# Sintetizador_BA_Analog.net
KiCad netlist of a schematic drawn in Altium Designer
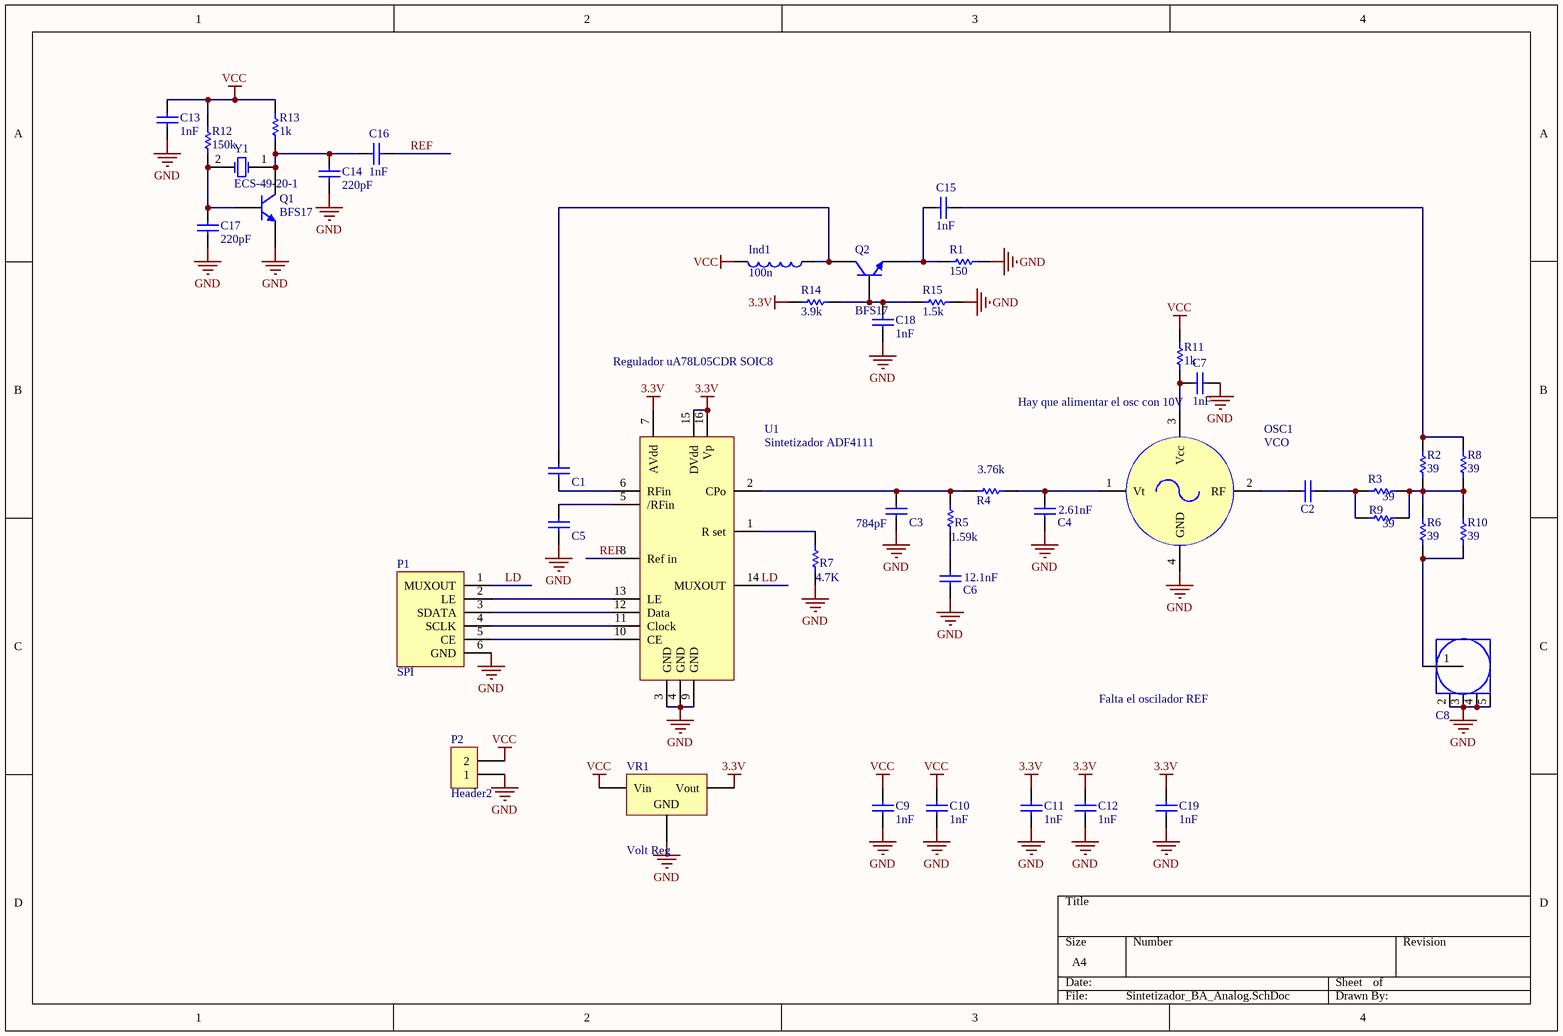
[diagram p0: Sintetizador_BA_Analog.SchDoc]

(export (version "E")
  (design (tool "Eeschema 10.0.6"))
  (components
    (comp (ref "C1") (value "Capacitor") (footprint "0805_CAP") (libsource (lib "epf") (part "Cap")))
    (comp (ref "C2") (value "Capacitor") (footprint "0805_CAP") (libsource (lib "epf") (part "Cap")))
    (comp (ref "C3")
      (value "784pF")
      (footprint "0805_CAP")
      (fields (field (name "Comment") "Capacitor"))
      (libsource (lib "epf") (part "Cap"))
    )
    (comp (ref "C4")
      (value "2.61nF")
      (footprint "0805_CAP")
      (fields (field (name "Comment") "Capacitor"))
      (libsource (lib "epf") (part "Cap"))
    )
    (comp (ref "C5") (value "Capacitor") (footprint "0805_CAP") (libsource (lib "epf") (part "Cap")))
    (comp (ref "C6")
      (value "12.1nF")
      (footprint "0805_CAP")
      (fields (field (name "Comment") "Capacitor"))
      (libsource (lib "epf") (part "Cap"))
    )
    (comp (ref "C7")
      (value "1nF")
      (footprint "0805_CAP")
      (fields (field (name "Comment") "Capacitor"))
      (libsource (lib "epf") (part "Cap"))
    )
    (comp (ref "C8") (value "SMA") (footprint "SMAL2") (libsource (lib "epf") (part "SMA")))
    (comp (ref "C9")
      (value "1nF")
      (footprint "0805_CAP")
      (fields (field (name "Comment") "Capacitor"))
      (libsource (lib "epf") (part "Cap"))
    )
    (comp (ref "C10")
      (value "1nF")
      (footprint "0805_CAP")
      (fields (field (name "Comment") "Capacitor"))
      (libsource (lib "epf") (part "Cap"))
    )
    (comp (ref "C11")
      (value "1nF")
      (footprint "0805_CAP")
      (fields (field (name "Comment") "Capacitor"))
      (libsource (lib "epf") (part "Cap"))
    )
    (comp (ref "C12")
      (value "1nF")
      (footprint "0805_CAP")
      (fields (field (name "Comment") "Capacitor"))
      (libsource (lib "epf") (part "Cap"))
    )
    (comp (ref "C13")
      (value "1nF")
      (footprint "0805_CAP")
      (fields (field (name "Comment") "Capacitor"))
      (libsource (lib "epf") (part "Cap"))
    )
    (comp (ref "C14")
      (value "220pF")
      (footprint "0805_CAP")
      (fields (field (name "Comment") "Capacitor"))
      (libsource (lib "epf") (part "Cap"))
    )
    (comp (ref "C15")
      (value "1nF")
      (footprint "0805_CAP")
      (fields (field (name "Comment") "Capacitor"))
      (libsource (lib "epf") (part "Cap"))
    )
    (comp (ref "C16")
      (value "1nF")
      (footprint "0805_CAP")
      (fields (field (name "Comment") "Capacitor"))
      (libsource (lib "epf") (part "Cap"))
    )
    (comp (ref "C17")
      (value "220pF")
      (footprint "0805_CAP")
      (fields (field (name "Comment") "Capacitor"))
      (libsource (lib "epf") (part "Cap"))
    )
    (comp (ref "C18")
      (value "1nF")
      (footprint "0805_CAP")
      (fields (field (name "Comment") "Capacitor"))
      (libsource (lib "epf") (part "Cap"))
    )
    (comp (ref "C19")
      (value "1nF")
      (footprint "0805_CAP")
      (fields (field (name "Comment") "Capacitor"))
      (libsource (lib "epf") (part "Cap"))
    )
    (comp (ref "Ind1")
      (value "Ind2")
      (footprint "NTH12_2")
      (fields (field (name "VALOR") "100n"))
      (libsource (lib "epf") (part "Ind2"))
    )
    (comp (ref "OSC1") (value "VCO") (footprint "V140MC03") (libsource (lib "epf") (part "V140MC03")))
    (comp (ref "P1") (value "SPI") (footprint "HeaderHx6") (libsource (lib "epf") (part "ADF_SPI_GND")))
    (comp (ref "P2") (value "Header2") (footprint "HeaderHx2") (libsource (lib "epf") (part "Header2")))
    (comp (ref "Q1")
      (value "BFS17")
      (footprint "SOT23")
      (description "NPN 1 GHz Wideband Transistor")
      (fields (field (name "PUBLISHER") "Altium Limited"))
      (libsource (lib "Philips Discrete BJT - RF Transistor") (part "BFS17"))
    )
    (comp (ref "Q2")
      (value "BFS17")
      (footprint "SOT23")
      (description "NPN 1 GHz Wideband Transistor")
      (fields (field (name "PUBLISHER") "Altium Limited"))
      (libsource (lib "Philips Discrete BJT - RF Transistor") (part "BFS17"))
    )
    (comp (ref "R1")
      (value "150")
      (footprint "0805_RES")
      (fields (field (name "Comment") "Resistor"))
      (libsource (lib "epf") (part "Res"))
    )
    (comp (ref "R2")
      (value "39")
      (footprint "0805_RES")
      (fields (field (name "Comment") "Resistor"))
      (libsource (lib "epf") (part "Res"))
    )
    (comp (ref "R3")
      (value "39")
      (footprint "0805_RES")
      (fields (field (name "Comment") "Resistor"))
      (libsource (lib "epf") (part "Res"))
    )
    (comp (ref "R4")
      (value "3.76k")
      (footprint "0805_RES")
      (fields (field (name "Comment") "Resistor"))
      (libsource (lib "epf") (part "Res"))
    )
    (comp (ref "R5")
      (value "1.59k")
      (footprint "0805_RES")
      (fields (field (name "Comment") "Resistor"))
      (libsource (lib "epf") (part "Res"))
    )
    (comp (ref "R6")
      (value "39")
      (footprint "0805_RES")
      (fields (field (name "Comment") "Resistor"))
      (libsource (lib "epf") (part "Res"))
    )
    (comp (ref "R7")
      (value "4.7K")
      (footprint "0805_RES")
      (fields (field (name "Comment") "Resistor"))
      (libsource (lib "epf") (part "Res"))
    )
    (comp (ref "R8")
      (value "39")
      (footprint "0805_RES")
      (fields (field (name "Comment") "Resistor"))
      (libsource (lib "epf") (part "Res"))
    )
    (comp (ref "R9")
      (value "39")
      (footprint "0805_RES")
      (fields (field (name "Comment") "Resistor"))
      (libsource (lib "epf") (part "Res"))
    )
    (comp (ref "R10")
      (value "39")
      (footprint "0805_RES")
      (fields (field (name "Comment") "Resistor"))
      (libsource (lib "epf") (part "Res"))
    )
    (comp (ref "R11")
      (value "1k")
      (footprint "0805_RES")
      (fields (field (name "Comment") "Resistor"))
      (libsource (lib "epf") (part "Res"))
    )
    (comp (ref "R12")
      (value "150k")
      (footprint "0805_RES")
      (fields (field (name "Comment") "Resistor"))
      (libsource (lib "epf") (part "Res"))
    )
    (comp (ref "R13")
      (value "1k")
      (footprint "0805_RES")
      (fields (field (name "Comment") "Resistor"))
      (libsource (lib "epf") (part "Res"))
    )
    (comp (ref "R14")
      (value "3.9k")
      (footprint "0805_RES")
      (fields (field (name "Comment") "Resistor"))
      (libsource (lib "epf") (part "Res"))
    )
    (comp (ref "R15")
      (value "1.5k")
      (footprint "0805_RES")
      (fields (field (name "Comment") "Resistor"))
      (libsource (lib "epf") (part "Res"))
    )
    (comp (ref "U1")
      (value "Sintetizador ADF4111")
      (footprint "TSSOP16")
      (libsource (lib "epf") (part "ADF4111"))
    )
    (comp (ref "VR1")
      (value "Volt Reg")
      (footprint "SOT-223 - M3")
      (description "Voltage Regulator")
      (fields (field (name "PUBLISHER") "Altium Limited"))
      (libsource (lib "epf") (part "Volt Reg"))
    )
    (comp (ref "Y1")
      (value "ECS-49-20-1")
      (footprint "HC-49U")
      (description "Crystal Oscillator")
      (fields (field (name "PUBLISHER") "Altium Limited"))
      (libsource (lib "ECS Crystal Oscillator") (part "ECS-49-20-1"))
    )
  )
  (nets
    (net (code "1") (name "/LD") (class "Default")
      (node (ref "P1") (pin "1") (pinfunction "MUXOUT_1") (pintype "passive"))
      (node (ref "U1") (pin "14") (pinfunction "MUXOUT_14") (pintype "passive"))
    )
    (net (code "2") (name "/REF") (class "Default")
      (node (ref "C16") (pin "1") (pinfunction "1_1") (pintype "passive"))
      (node (ref "U1") (pin "8") (pinfunction "Ref_in_8") (pintype "passive"))
    )
    (net (code "3") (name "3.3V") (class "Default")
      (node (ref "C11") (pin "2") (pinfunction "2_2") (pintype "passive"))
      (node (ref "C12") (pin "2") (pinfunction "2_2") (pintype "passive"))
      (node (ref "C19") (pin "2") (pinfunction "2_2") (pintype "passive"))
      (node (ref "R14") (pin "1") (pinfunction "1_1") (pintype "passive"))
      (node (ref "U1") (pin "15") (pinfunction "DVdd_15") (pintype "passive"))
      (node (ref "U1") (pin "16") (pinfunction "Vp_16") (pintype "passive"))
      (node (ref "U1") (pin "7") (pinfunction "AVdd_7") (pintype "passive"))
      (node (ref "VR1") (pin "3") (pinfunction "Vout_3") (pintype "passive"))
    )
    (net (code "4") (name "GND") (class "Default")
      (node (ref "C10") (pin "1") (pinfunction "1_1") (pintype "passive"))
      (node (ref "C11") (pin "1") (pinfunction "1_1") (pintype "passive"))
      (node (ref "C12") (pin "1") (pinfunction "1_1") (pintype "passive"))
      (node (ref "C13") (pin "1") (pinfunction "1_1") (pintype "passive"))
      (node (ref "C14") (pin "2") (pinfunction "2_2") (pintype "passive"))
      (node (ref "C17") (pin "1") (pinfunction "1_1") (pintype "passive"))
      (node (ref "C18") (pin "1") (pinfunction "1_1") (pintype "passive"))
      (node (ref "C19") (pin "1") (pinfunction "1_1") (pintype "passive"))
      (node (ref "C3") (pin "1") (pinfunction "1_1") (pintype "passive"))
      (node (ref "C4") (pin "1") (pinfunction "1_1") (pintype "passive"))
      (node (ref "C5") (pin "1") (pinfunction "1_1") (pintype "passive"))
      (node (ref "C6") (pin "1") (pinfunction "1_1") (pintype "passive"))
      (node (ref "C7") (pin "1") (pinfunction "1_1") (pintype "passive"))
      (node (ref "C8") (pin "2") (pinfunction "GND_2") (pintype "passive"))
      (node (ref "C8") (pin "3") (pinfunction "GND_3") (pintype "passive"))
      (node (ref "C8") (pin "4") (pinfunction "GND_4") (pintype "passive"))
      (node (ref "C8") (pin "5") (pinfunction "GND_5") (pintype "passive"))
      (node (ref "C9") (pin "1") (pinfunction "1_1") (pintype "passive"))
      (node (ref "OSC1") (pin "4") (pinfunction "GND_4") (pintype "passive"))
      (node (ref "P1") (pin "6") (pinfunction "GND_6") (pintype "passive"))
      (node (ref "P2") (pin "1") (pinfunction "1_1") (pintype "passive"))
      (node (ref "Q1") (pin "2") (pinfunction "E_2") (pintype "passive"))
      (node (ref "R1") (pin "2") (pinfunction "2_2") (pintype "passive"))
      (node (ref "R15") (pin "2") (pinfunction "2_2") (pintype "passive"))
      (node (ref "R7") (pin "2") (pinfunction "2_2") (pintype "passive"))
      (node (ref "U1") (pin "3") (pinfunction "GND_3") (pintype "passive"))
      (node (ref "U1") (pin "4") (pinfunction "GND_4") (pintype "passive"))
      (node (ref "U1") (pin "9") (pinfunction "GND_9") (pintype "passive"))
      (node (ref "VR1") (pin "2") (pinfunction "GND_2") (pintype "passive"))
    )
    (net (code "5") (name "Net-(C2-Pad1)") (class "Default")
      (node (ref "C2") (pin "1") (pinfunction "1_1") (pintype "passive"))
      (node (ref "R3") (pin "1") (pinfunction "1_1") (pintype "passive"))
      (node (ref "R9") (pin "1") (pinfunction "1_1") (pintype "passive"))
    )
    (net (code "6") (name "Net-(C6-Pad2)") (class "Default")
      (node (ref "C6") (pin "2") (pinfunction "2_2") (pintype "passive"))
      (node (ref "R5") (pin "2") (pinfunction "2_2") (pintype "passive"))
    )
    (net (code "7") (name "Net-(C8-RF)") (class "Default")
      (node (ref "C8") (pin "1") (pinfunction "RF_1") (pintype "passive"))
      (node (ref "R10") (pin "1") (pinfunction "1_1") (pintype "passive"))
      (node (ref "R6") (pin "1") (pinfunction "1_1") (pintype "passive"))
    )
    (net (code "8") (name "Net-(C15-Pad2)") (class "Default")
      (node (ref "C15") (pin "2") (pinfunction "2_2") (pintype "passive"))
      (node (ref "R2") (pin "2") (pinfunction "2_2") (pintype "passive"))
      (node (ref "R8") (pin "2") (pinfunction "2_2") (pintype "passive"))
    )
    (net (code "9") (name "Net-(OSC1-RF)") (class "Default")
      (node (ref "C2") (pin "2") (pinfunction "2_2") (pintype "passive"))
      (node (ref "OSC1") (pin "2") (pinfunction "RF_2") (pintype "passive"))
    )
    (net (code "10") (name "Net-(OSC1-Vcc)") (class "Default")
      (node (ref "C7") (pin "2") (pinfunction "2_2") (pintype "passive"))
      (node (ref "OSC1") (pin "3") (pinfunction "Vcc_3") (pintype "passive"))
      (node (ref "R11") (pin "2") (pinfunction "2_2") (pintype "passive"))
    )
    (net (code "11") (name "Net-(OSC1-Vt)") (class "Default")
      (node (ref "C4") (pin "2") (pinfunction "2_2") (pintype "passive"))
      (node (ref "OSC1") (pin "1") (pinfunction "Vt_1") (pintype "passive"))
      (node (ref "R4") (pin "2") (pinfunction "2_2") (pintype "passive"))
    )
    (net (code "12") (name "Net-(P1-CE)") (class "Default")
      (node (ref "P1") (pin "5") (pinfunction "CE_5") (pintype "passive"))
      (node (ref "U1") (pin "10") (pinfunction "CE_10") (pintype "passive"))
    )
    (net (code "13") (name "Net-(P1-LE)") (class "Default")
      (node (ref "P1") (pin "2") (pinfunction "LE_2") (pintype "passive"))
      (node (ref "U1") (pin "13") (pinfunction "LE_13") (pintype "passive"))
    )
    (net (code "14") (name "Net-(P1-SCLK)") (class "Default")
      (node (ref "P1") (pin "4") (pinfunction "SCLK_4") (pintype "passive"))
      (node (ref "U1") (pin "11") (pinfunction "Clock_11") (pintype "passive"))
    )
    (net (code "15") (name "Net-(P1-SDATA)") (class "Default")
      (node (ref "P1") (pin "3") (pinfunction "SDATA_3") (pintype "passive"))
      (node (ref "U1") (pin "12") (pinfunction "Data_12") (pintype "passive"))
    )
    (net (code "16") (name "Net-(Q1-B)") (class "Default")
      (node (ref "C17") (pin "2") (pinfunction "2_2") (pintype "passive"))
      (node (ref "Q1") (pin "1") (pinfunction "B_1") (pintype "passive"))
      (node (ref "R12") (pin "2") (pinfunction "2_2") (pintype "passive"))
      (node (ref "Y1") (pin "2") (pinfunction "OSC2_2") (pintype "passive"))
    )
    (net (code "17") (name "Net-(Q1-C)") (class "Default")
      (node (ref "C14") (pin "1") (pinfunction "1_1") (pintype "passive"))
      (node (ref "C16") (pin "2") (pinfunction "2_2") (pintype "passive"))
      (node (ref "Q1") (pin "3") (pinfunction "C_3") (pintype "passive"))
      (node (ref "R13") (pin "2") (pinfunction "2_2") (pintype "passive"))
      (node (ref "Y1") (pin "1") (pinfunction "OSC1_1") (pintype "passive"))
    )
    (net (code "18") (name "Net-(Q2-B)") (class "Default")
      (node (ref "C18") (pin "2") (pinfunction "2_2") (pintype "passive"))
      (node (ref "Q2") (pin "1") (pinfunction "B_1") (pintype "passive"))
      (node (ref "R14") (pin "2") (pinfunction "2_2") (pintype "passive"))
      (node (ref "R15") (pin "1") (pinfunction "1_1") (pintype "passive"))
    )
    (net (code "19") (name "Net-(Q2-C)") (class "Default")
      (node (ref "C1") (pin "2") (pinfunction "2_2") (pintype "passive"))
      (node (ref "Ind1") (pin "1") (pinfunction "1_1") (pintype "passive"))
      (node (ref "Q2") (pin "3") (pinfunction "C_3") (pintype "passive"))
    )
    (net (code "20") (name "Net-(Q2-E)") (class "Default")
      (node (ref "C15") (pin "1") (pinfunction "1_1") (pintype "passive"))
      (node (ref "Q2") (pin "2") (pinfunction "E_2") (pintype "passive"))
      (node (ref "R1") (pin "1") (pinfunction "1_1") (pintype "passive"))
    )
    (net (code "21") (name "Net-(R10-Pad2)") (class "Default")
      (node (ref "R10") (pin "2") (pinfunction "2_2") (pintype "passive"))
      (node (ref "R2") (pin "1") (pinfunction "1_1") (pintype "passive"))
      (node (ref "R3") (pin "2") (pinfunction "2_2") (pintype "passive"))
      (node (ref "R6") (pin "2") (pinfunction "2_2") (pintype "passive"))
      (node (ref "R8") (pin "1") (pinfunction "1_1") (pintype "passive"))
      (node (ref "R9") (pin "2") (pinfunction "2_2") (pintype "passive"))
    )
    (net (code "22") (name "Net-(U1-CPo)") (class "Default")
      (node (ref "C3") (pin "2") (pinfunction "2_2") (pintype "passive"))
      (node (ref "R4") (pin "1") (pinfunction "1_1") (pintype "passive"))
      (node (ref "R5") (pin "1") (pinfunction "1_1") (pintype "passive"))
      (node (ref "U1") (pin "2") (pinfunction "CPo_2") (pintype "passive"))
    )
    (net (code "23") (name "Net-(U1-RFin)") (class "Default")
      (node (ref "C1") (pin "1") (pinfunction "1_1") (pintype "passive"))
      (node (ref "U1") (pin "6") (pinfunction "RFin_6") (pintype "passive"))
    )
    (net (code "24") (name "Net-(U1-R_set)") (class "Default")
      (node (ref "R7") (pin "1") (pinfunction "1_1") (pintype "passive"))
      (node (ref "U1") (pin "1") (pinfunction "R_set_1") (pintype "passive"))
    )
    (net (code "25") (name "Net-(U1-{slash}RFin)") (class "Default")
      (node (ref "C5") (pin "2") (pinfunction "2_2") (pintype "passive"))
      (node (ref "U1") (pin "5") (pinfunction "/RFin_5") (pintype "passive"))
    )
    (net (code "26") (name "VCC") (class "Default")
      (node (ref "C10") (pin "2") (pinfunction "2_2") (pintype "passive"))
      (node (ref "C13") (pin "2") (pinfunction "2_2") (pintype "passive"))
      (node (ref "C9") (pin "2") (pinfunction "2_2") (pintype "passive"))
      (node (ref "Ind1") (pin "2") (pinfunction "2_2") (pintype "passive"))
      (node (ref "P2") (pin "2") (pinfunction "2_2") (pintype "passive"))
      (node (ref "R11") (pin "1") (pinfunction "1_1") (pintype "passive"))
      (node (ref "R12") (pin "1") (pinfunction "1_1") (pintype "passive"))
      (node (ref "R13") (pin "1") (pinfunction "1_1") (pintype "passive"))
      (node (ref "VR1") (pin "1") (pinfunction "Vin_1") (pintype "passive"))
    )
  )
)
